# Zhonji_ai8051__Board1_Schematic1__2_P2.net
KiCad netlist of a schematic drawn in Altium Designer
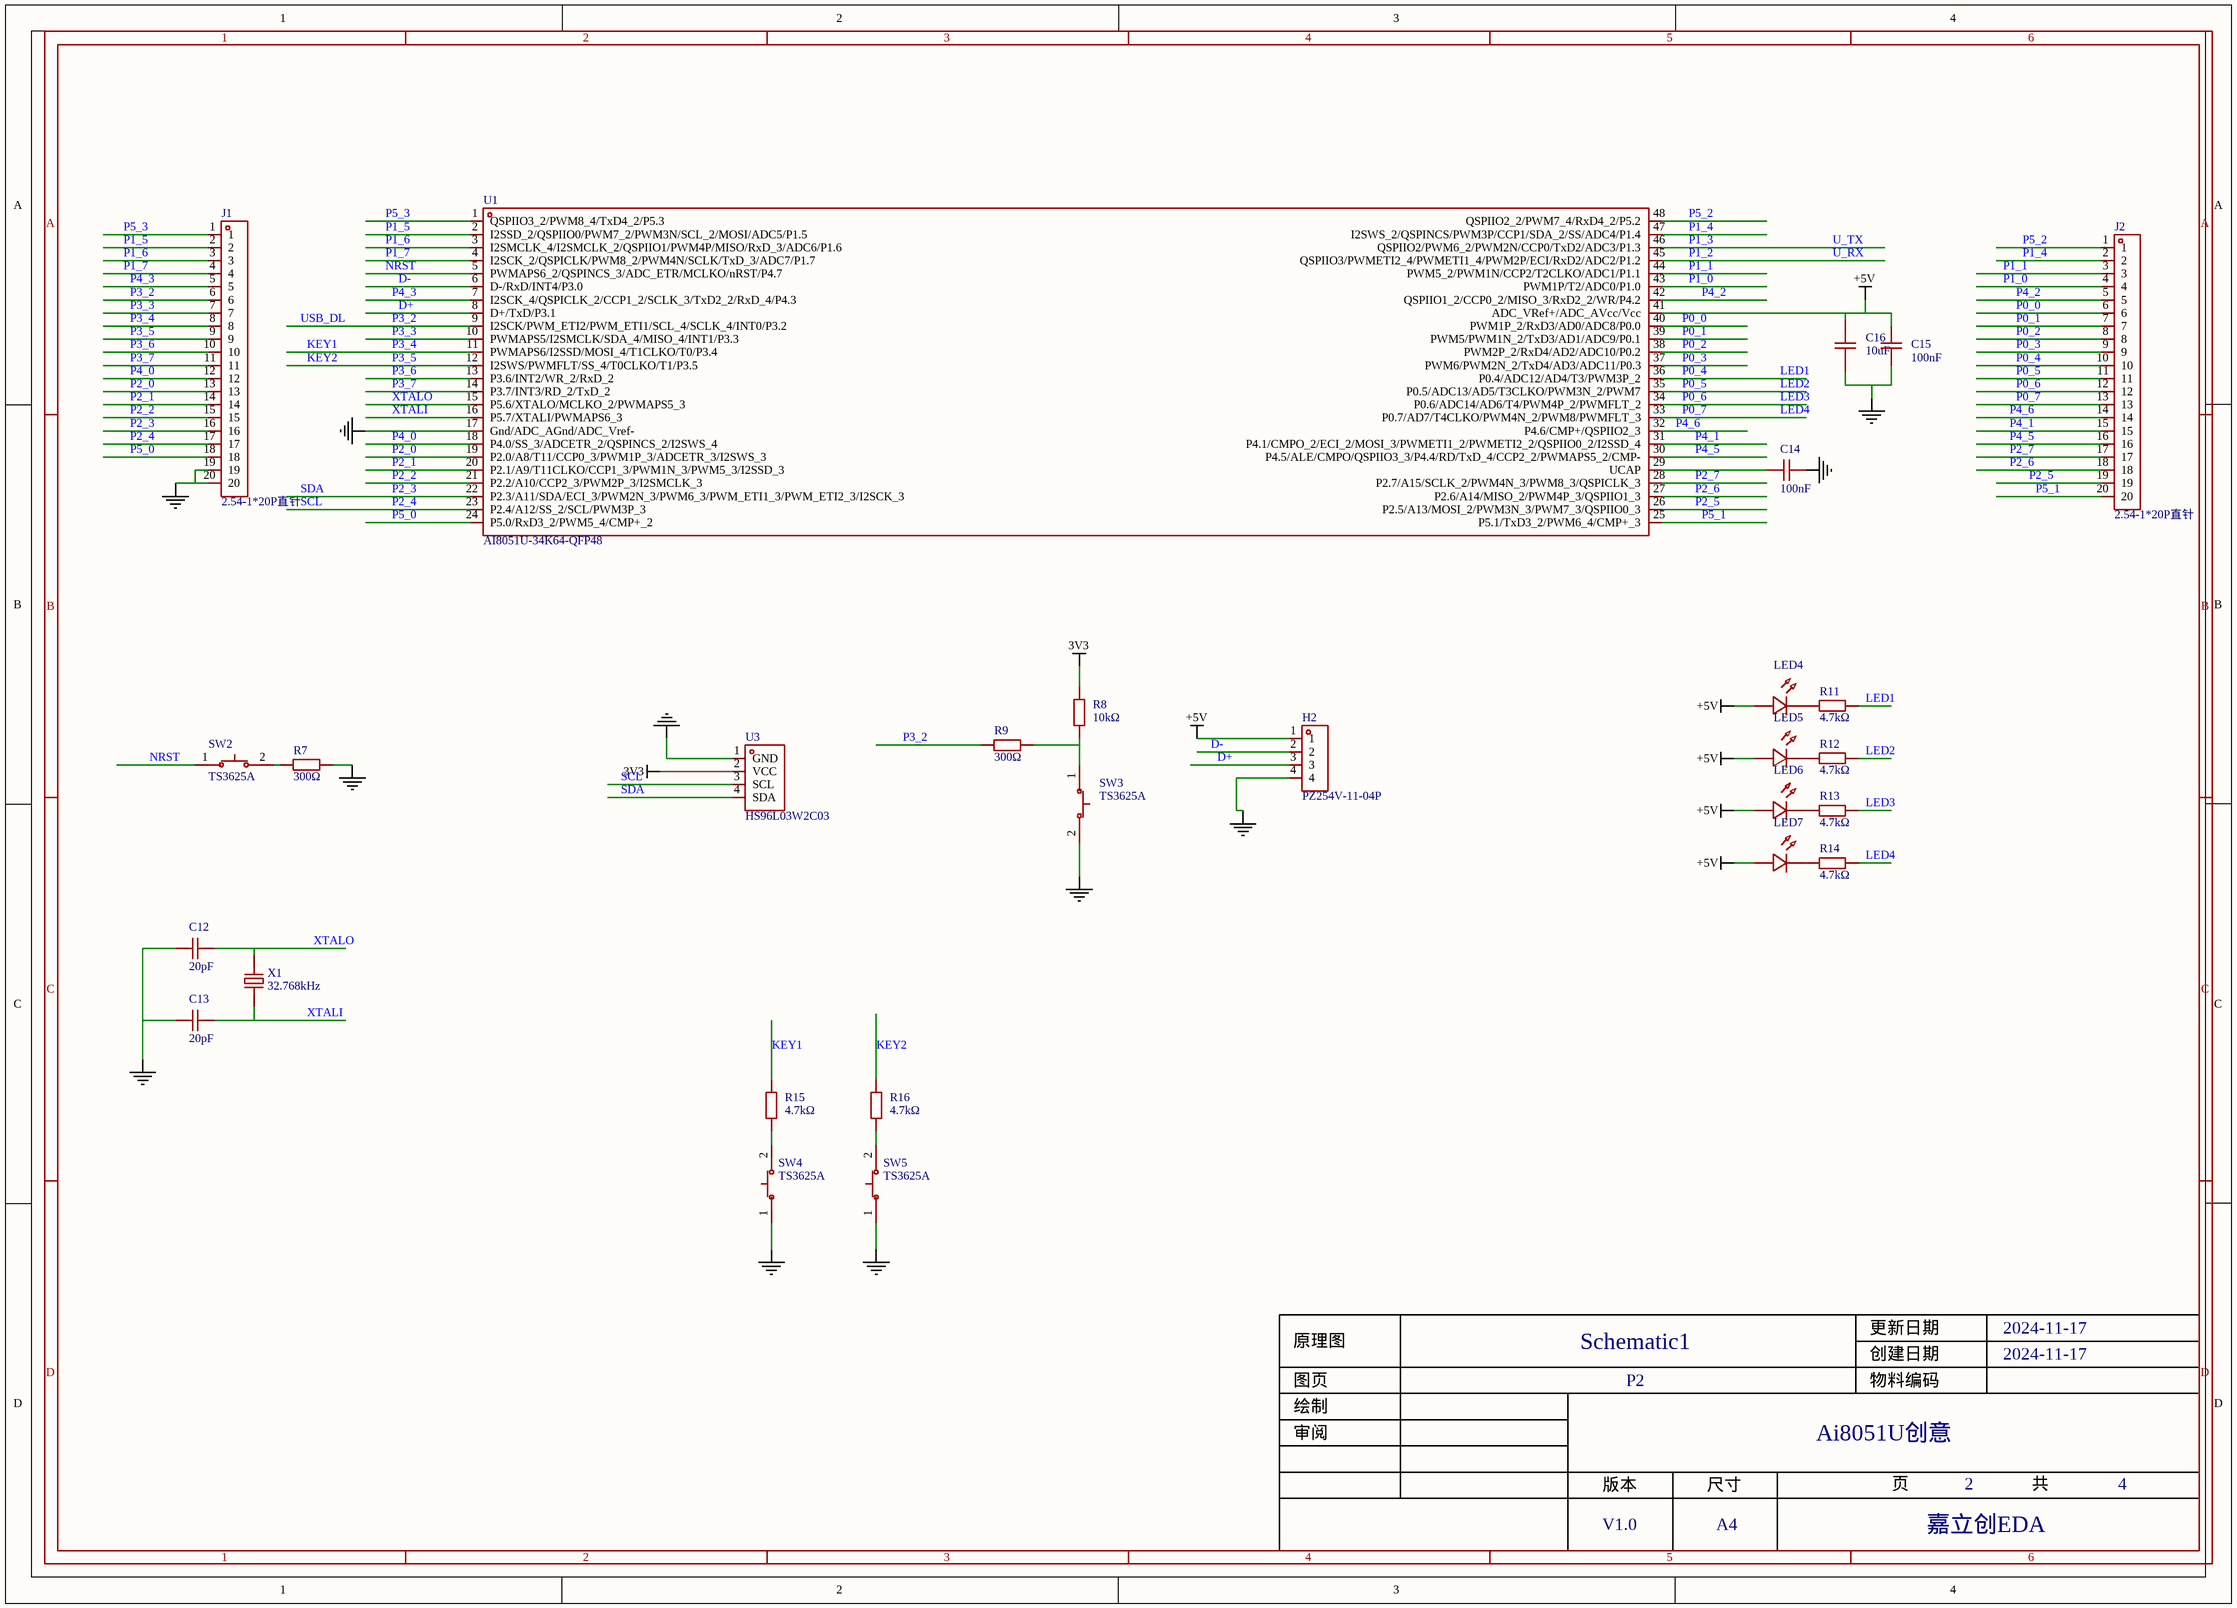
[diagram p0: Zhonji_ai8051__Board1_Schematic1__2_P2.schdoc]

(export (version "E")
  (design (tool "Eeschema 10.0.6"))
  (components
    (comp (ref "C12")
      (value "20pF")
      (footprint "C0603")
      (description "容值:20pF;精度:±5%;额定电压:50V;材质(温度系数):C0G;")
      (fields
        (field (name "MANUFACTURER") "SAMSUNG(三星)")
        (field (name "MANUFACTURER PART") "CL10C200JB8NNNC")
      )
      (libsource (lib "altium-import") (part "root_0_CL10C200JB8NNNC_"))
    )
    (comp (ref "C13")
      (value "20pF")
      (footprint "C0603")
      (description "容值:20pF;精度:±5%;额定电压:50V;材质(温度系数):C0G;")
      (fields
        (field (name "MANUFACTURER") "SAMSUNG(三星)")
        (field (name "MANUFACTURER PART") "CL10C200JB8NNNC")
      )
      (libsource (lib "altium-import") (part "root_0_CL10C200JB8NNNC_"))
    )
    (comp (ref "C14")
      (value "100nF")
      (footprint "C0603")
      (description "容值:100nF;精度:±10%;额定电压:50V;材质(温度系数):2X1;")
      (fields
        (field (name "MANUFACTURER") "TORCH(火炬)")
        (field (name "MANUFACTURER PART") "CT41G-0603-2X1-50V-0.1μF-K(N)")
      )
      (libsource (lib "altium-import") (part "root_2_CT41G-0603-2X1-50V-0.1μF-K(N)_"))
    )
    (comp (ref "C15")
      (value "100nF")
      (footprint "C0603")
      (description "容值:100nF;精度:±10%;额定电压:50V;材质(温度系数):2X1;")
      (fields
        (field (name "MANUFACTURER") "TORCH(火炬)")
        (field (name "MANUFACTURER PART") "CT41G-0603-2X1-50V-0.1μF-K(N)")
      )
      (libsource (lib "altium-import") (part "root_1_CT41G-0603-2X1-50V-0.1μF-K(N)_"))
    )
    (comp (ref "C16")
      (value "10uF")
      (footprint "C0603")
      (description "容值:10uF;精度:±20%;额定电压:25V;材质(温度系数):X5R;")
      (fields
        (field (name "MANUFACTURER") "SAMSUNG(三星)")
        (field (name "MANUFACTURER PART") "CL10A106MA8NRNC")
      )
      (libsource (lib "altium-import") (part "root_1_CL10A106MA8NRNC_"))
    )
    (comp (ref "H2")
      (value "PZ254V-11-04P")
      (footprint "HDR-TH_4P-P2.54-V-M")
      (fields (field (name "MANUFACTURER") "XFCN(兴飞)"))
      (libsource (lib "altium-import") (part "root_0_PZ254V-11-04P_"))
    )
    (comp (ref "J1")
      (value "2.54-1*20P直针")
      (footprint "HDR-TH_20P-P2.54-V-M-1")
      (fields (field (name "MANUFACTURER") "BOOMELE(博穆精密)"))
      (libsource (lib "altium-import") (part "root_0_2.54-1*20P直针_"))
    )
    (comp (ref "J2")
      (value "2.54-1*20P直针")
      (footprint "HDR-TH_20P-P2.54-V-M-1")
      (fields (field (name "MANUFACTURER") "BOOMELE(博穆精密)"))
      (libsource (lib "altium-import") (part "root_0_2.54-1*20P直针_"))
    )
    (comp (ref "LED4")
      (value "LED_0603-B")
      (footprint "LED_0603")
      (libsource (lib "altium-import") (part "root_0_LED_0603-B_"))
    )
    (comp (ref "LED5")
      (value "LED_0603-B")
      (footprint "LED_0603")
      (libsource (lib "altium-import") (part "root_0_LED_0603-B_"))
    )
    (comp (ref "LED6")
      (value "LED_0603-B")
      (footprint "LED_0603")
      (libsource (lib "altium-import") (part "root_0_LED_0603-B_"))
    )
    (comp (ref "LED7")
      (value "LED_0603-B")
      (footprint "LED_0603")
      (libsource (lib "altium-import") (part "root_0_LED_0603-B_"))
    )
    (comp (ref "R7")
      (value "300Ω")
      (footprint "R0603")
      (description "电阻类型:厚膜电阻;阻值:300Ω;精度:±1%;功率:100mW;最大工作电压:75V;温度系数:±100ppm/℃;")
      (fields
        (field (name "MANUFACTURER") "UNI-ROYAL(厚声)")
        (field (name "MANUFACTURER PART") "0603WAF3000T5E")
      )
      (libsource (lib "altium-import") (part "root_0_0603WAF3000T5E_"))
    )
    (comp (ref "R8")
      (value "10kΩ")
      (footprint "R0603")
      (description "电阻类型:厚膜电阻;阻值:10kΩ;精度:±1%;功率:100mW;最大工作电压:75V;温度系数:±100ppm/℃;")
      (fields
        (field (name "MANUFACTURER") "UNI-ROYAL(厚声)")
        (field (name "MANUFACTURER PART") "0603WAF1002T5E")
      )
      (libsource (lib "altium-import") (part "root_1_0603WAF1002T5E_"))
    )
    (comp (ref "R9")
      (value "300Ω")
      (footprint "R0603")
      (description "电阻类型:厚膜电阻;阻值:300Ω;精度:±1%;功率:100mW;最大工作电压:75V;温度系数:±100ppm/℃;")
      (fields
        (field (name "MANUFACTURER") "UNI-ROYAL(厚声)")
        (field (name "MANUFACTURER PART") "0603WAF3000T5E")
      )
      (libsource (lib "altium-import") (part "root_0_0603WAF3000T5E_"))
    )
    (comp (ref "R11")
      (value "4.7kΩ")
      (footprint "R0603")
      (description "电阻类型:厚膜电阻;阻值:4.7kΩ;精度:±1%;功率:100mW;最大工作电压:75V;温度系数:±100ppm/℃;")
      (fields
        (field (name "MANUFACTURER") "UNI-ROYAL(厚声)")
        (field (name "MANUFACTURER PART") "0603WAF4701T5E")
      )
      (libsource (lib "altium-import") (part "root_0_0603WAF4701T5E_"))
    )
    (comp (ref "R12")
      (value "4.7kΩ")
      (footprint "R0603")
      (description "电阻类型:厚膜电阻;阻值:4.7kΩ;精度:±1%;功率:100mW;最大工作电压:75V;温度系数:±100ppm/℃;")
      (fields
        (field (name "MANUFACTURER") "UNI-ROYAL(厚声)")
        (field (name "MANUFACTURER PART") "0603WAF4701T5E")
      )
      (libsource (lib "altium-import") (part "root_0_0603WAF4701T5E_"))
    )
    (comp (ref "R13")
      (value "4.7kΩ")
      (footprint "R0603")
      (description "电阻类型:厚膜电阻;阻值:4.7kΩ;精度:±1%;功率:100mW;最大工作电压:75V;温度系数:±100ppm/℃;")
      (fields
        (field (name "MANUFACTURER") "UNI-ROYAL(厚声)")
        (field (name "MANUFACTURER PART") "0603WAF4701T5E")
      )
      (libsource (lib "altium-import") (part "root_0_0603WAF4701T5E_"))
    )
    (comp (ref "R14")
      (value "4.7kΩ")
      (footprint "R0603")
      (description "电阻类型:厚膜电阻;阻值:4.7kΩ;精度:±1%;功率:100mW;最大工作电压:75V;温度系数:±100ppm/℃;")
      (fields
        (field (name "MANUFACTURER") "UNI-ROYAL(厚声)")
        (field (name "MANUFACTURER PART") "0603WAF4701T5E")
      )
      (libsource (lib "altium-import") (part "root_0_0603WAF4701T5E_"))
    )
    (comp (ref "R15")
      (value "4.7kΩ")
      (footprint "R0603")
      (description "电阻类型:厚膜电阻;阻值:4.7kΩ;精度:±1%;功率:100mW;最大工作电压:75V;温度系数:±100ppm/℃;")
      (fields
        (field (name "MANUFACTURER") "UNI-ROYAL(厚声)")
        (field (name "MANUFACTURER PART") "0603WAF4701T5E")
      )
      (libsource (lib "altium-import") (part "root_1_0603WAF4701T5E_"))
    )
    (comp (ref "R16")
      (value "4.7kΩ")
      (footprint "R0603")
      (description "电阻类型:厚膜电阻;阻值:4.7kΩ;精度:±1%;功率:100mW;最大工作电压:75V;温度系数:±100ppm/℃;")
      (fields
        (field (name "MANUFACTURER") "UNI-ROYAL(厚声)")
        (field (name "MANUFACTURER PART") "0603WAF4701T5E")
      )
      (libsource (lib "altium-import") (part "root_1_0603WAF4701T5E_"))
    )
    (comp (ref "SW2")
      (value "TS3625A")
      (footprint "KEY-SMD_L6.0-W3.5-LS8.4")
      (fields (field (name "MANUFACTURER") "SHOU HAN(首韩)"))
      (libsource (lib "altium-import") (part "root_0_TS3625A_"))
    )
    (comp (ref "SW3")
      (value "TS3625A")
      (footprint "KEY-SMD_L6.0-W3.5-LS8.4")
      (fields (field (name "MANUFACTURER") "SHOU HAN(首韩)"))
      (libsource (lib "altium-import") (part "root_3_TS3625A_"))
    )
    (comp (ref "SW4")
      (value "TS3625A")
      (footprint "KEY-SMD_L6.0-W3.5-LS8.4")
      (fields (field (name "MANUFACTURER") "SHOU HAN(首韩)"))
      (libsource (lib "altium-import") (part "root_1_TS3625A_"))
    )
    (comp (ref "SW5")
      (value "TS3625A")
      (footprint "KEY-SMD_L6.0-W3.5-LS8.4")
      (fields (field (name "MANUFACTURER") "SHOU HAN(首韩)"))
      (libsource (lib "altium-import") (part "root_1_TS3625A_"))
    )
    (comp (ref "U1")
      (value "AI8051U-34K64-QFP48")
      (footprint "LQFP-48_L7.0-W7.0-P0.50-LS9.0-BL_1")
      (description "硬件浮点/硬件三角函数 跑100MHz, 32位8051-CPU 跑 42MHz，PWM 有硬件移相功能，DMA支持外设到外设，DMA支持PWM")
      (fields (field (name "MANUFACTURER") "STC"))
      (libsource (lib "altium-import") (part "root_0_AI8051U-34K64-QFP48_"))
    )
    (comp (ref "U3")
      (value "HS96L03W2C03")
      (footprint "OLED-TH_L27.8-W27.2-P2.54_C9900033791")
      (description "主控芯片:SSD1315;接口类型:I2C;尺寸(inch):0.96;像素分辨率:128x64;")
      (fields (field (name "MANUFACTURER") "HS(汉昇)"))
      (libsource (lib "altium-import") (part "root_0_HS96L03W2C03_"))
    )
    (comp (ref "X1")
      (value "32.768kHz")
      (footprint "OSC-SMD_L3.2-W1.5")
      (description "晶振类型:贴片晶振;频率:32.768kHz;常温频差:±20ppm;外接负载电容:12.5pF;频率稳定度(全温):-;")
      (fields (field (name "MANUFACTURER") "YXC(扬兴晶振)") (field (name "MANUFACTURER PART") "X321532768KGD2SI"))
      (libsource (lib "altium-import") (part "root_1_X321532768KGD2SI_"))
    )
  )
  (nets
    (net (code "1") (name "+5V") (class "Default")
      (node (ref "C15") (pin "2") (pinfunction "2_2") (pintype "passive"))
      (node (ref "C16") (pin "2") (pinfunction "2_2") (pintype "passive"))
      (node (ref "H2") (pin "1") (pinfunction "1_1") (pintype "passive"))
      (node (ref "LED4") (pin "2") (pinfunction "A_2") (pintype "passive"))
      (node (ref "LED5") (pin "2") (pinfunction "A_2") (pintype "passive"))
      (node (ref "LED6") (pin "2") (pinfunction "A_2") (pintype "passive"))
      (node (ref "LED7") (pin "2") (pinfunction "A_2") (pintype "passive"))
      (node (ref "U1") (pin "41") (pinfunction "ADC_VRef+/ADC_AVcc/Vcc_41") (pintype "passive"))
    )
    (net (code "2") (name "/D+") (class "Default")
      (node (ref "H2") (pin "3") (pinfunction "3_3") (pintype "passive"))
      (node (ref "U1") (pin "8") (pinfunction "D+/TxD/P3.1_8") (pintype "passive"))
    )
    (net (code "3") (name "/D-") (class "Default")
      (node (ref "H2") (pin "2") (pinfunction "2_2") (pintype "passive"))
      (node (ref "U1") (pin "6") (pinfunction "D-/RxD/INT4/P3.0_6") (pintype "passive"))
    )
    (net (code "4") (name "/KEY1") (class "Default")
      (node (ref "J1") (pin "8") (pinfunction "8_8") (pintype "passive"))
      (node (ref "R15") (pin "2") (pinfunction "2_2") (pintype "passive"))
      (node (ref "U1") (pin "11") (pinfunction "PWMAPS6/I2SSD/MOSI_4/T1CLKO/T0/P3.4_11") (pintype "passive"))
    )
    (net (code "5") (name "/KEY2") (class "Default")
      (node (ref "J1") (pin "9") (pinfunction "9_9") (pintype "passive"))
      (node (ref "R16") (pin "2") (pinfunction "2_2") (pintype "passive"))
      (node (ref "U1") (pin "12") (pinfunction "I2SWS/PWMFLT/SS_4/T0CLKO/T1/P3.5_12") (pintype "passive"))
    )
    (net (code "6") (name "/LED1") (class "Default")
      (node (ref "J2") (pin "10") (pinfunction "10_10") (pintype "passive"))
      (node (ref "R11") (pin "2") (pinfunction "2_2") (pintype "passive"))
      (node (ref "U1") (pin "36") (pinfunction "P0.4/ADC12/AD4/T3/PWM3P_2_36") (pintype "passive"))
    )
    (net (code "7") (name "/LED2") (class "Default")
      (node (ref "J2") (pin "11") (pinfunction "11_11") (pintype "passive"))
      (node (ref "R12") (pin "2") (pinfunction "2_2") (pintype "passive"))
      (node (ref "U1") (pin "35") (pinfunction "P0.5/ADC13/AD5/T3CLKO/PWM3N_2/PWM7_35") (pintype "passive"))
    )
    (net (code "8") (name "/LED3") (class "Default")
      (node (ref "J2") (pin "12") (pinfunction "12_12") (pintype "passive"))
      (node (ref "R13") (pin "2") (pinfunction "2_2") (pintype "passive"))
      (node (ref "U1") (pin "34") (pinfunction "P0.6/ADC14/AD6/T4/PWM4P_2/PWMFLT_2_34") (pintype "passive"))
    )
    (net (code "9") (name "/LED4") (class "Default")
      (node (ref "J2") (pin "13") (pinfunction "13_13") (pintype "passive"))
      (node (ref "R14") (pin "2") (pinfunction "2_2") (pintype "passive"))
      (node (ref "U1") (pin "33") (pinfunction "P0.7/AD7/T4CLKO/PWM4N_2/PWM8/PWMFLT_3_33") (pintype "passive"))
    )
    (net (code "10") (name "/NRST") (class "Default")
      (node (ref "SW2") (pin "1") (pinfunction "1_1") (pintype "passive"))
      (node (ref "U1") (pin "5") (pinfunction "PWMAPS6_2/QSPINCS_3/ADC_ETR/MCLKO/nRST/P4.7_5") (pintype "passive"))
    )
    (net (code "11") (name "/P0_0") (class "Default")
      (node (ref "J2") (pin "6") (pinfunction "6_6") (pintype "passive"))
      (node (ref "U1") (pin "40") (pinfunction "PWM1P_2/RxD3/AD0/ADC8/P0.0_40") (pintype "passive"))
    )
    (net (code "12") (name "/P0_1") (class "Default")
      (node (ref "J2") (pin "7") (pinfunction "7_7") (pintype "passive"))
      (node (ref "U1") (pin "39") (pinfunction "PWM5/PWM1N_2/TxD3/AD1/ADC9/P0.1_39") (pintype "passive"))
    )
    (net (code "13") (name "/P0_2") (class "Default")
      (node (ref "J2") (pin "8") (pinfunction "8_8") (pintype "passive"))
      (node (ref "U1") (pin "38") (pinfunction "PWM2P_2/RxD4/AD2/ADC10/P0.2_38") (pintype "passive"))
    )
    (net (code "14") (name "/P0_3") (class "Default")
      (node (ref "J2") (pin "9") (pinfunction "9_9") (pintype "passive"))
      (node (ref "U1") (pin "37") (pinfunction "PWM6/PWM2N_2/TxD4/AD3/ADC11/P0.3_37") (pintype "passive"))
    )
    (net (code "15") (name "/P1_0") (class "Default")
      (node (ref "J2") (pin "4") (pinfunction "4_4") (pintype "passive"))
      (node (ref "U1") (pin "43") (pinfunction "PWM1P/T2/ADC0/P1.0_43") (pintype "passive"))
    )
    (net (code "16") (name "/P1_1") (class "Default")
      (node (ref "J2") (pin "3") (pinfunction "3_3") (pintype "passive"))
      (node (ref "U1") (pin "44") (pinfunction "PWM5_2/PWM1N/CCP2/T2CLKO/ADC1/P1.1_44") (pintype "passive"))
    )
    (net (code "17") (name "/P1_2") (class "Default")
      (node (ref "U1") (pin "45") (pinfunction "QSPIIO3/PWMETI2_4/PWMETI1_4/PWM2P/ECI/RxD2/ADC2/P1.2_45") (pintype "passive"))
    )
    (net (code "18") (name "/P1_3") (class "Default")
      (node (ref "U1") (pin "46") (pinfunction "QSPIIO2/PWM6_2/PWM2N/CCP0/TxD2/ADC3/P1.3_46") (pintype "passive"))
    )
    (net (code "19") (name "/P1_4") (class "Default")
      (node (ref "J2") (pin "2") (pinfunction "2_2") (pintype "passive"))
      (node (ref "U1") (pin "47") (pinfunction "I2SWS_2/QSPINCS/PWM3P/CCP1/SDA_2/SS/ADC4/P1.4_47") (pintype "passive"))
    )
    (net (code "20") (name "/P1_5") (class "Default")
      (node (ref "J1") (pin "2") (pinfunction "2_2") (pintype "passive"))
      (node (ref "U1") (pin "2") (pinfunction "I2SSD_2/QSPIIO0/PWM7_2/PWM3N/SCL_2/MOSI/ADC5/P1.5_2") (pintype "passive"))
    )
    (net (code "21") (name "/P1_6") (class "Default")
      (node (ref "J1") (pin "3") (pinfunction "3_3") (pintype "passive"))
      (node (ref "U1") (pin "3") (pinfunction "I2SMCLK_4/I2SMCLK_2/QSPIIO1/PWM4P/MISO/RxD_3/ADC6/P1.6_3") (pintype "passive"))
    )
    (net (code "22") (name "/P1_7") (class "Default")
      (node (ref "J1") (pin "4") (pinfunction "4_4") (pintype "passive"))
      (node (ref "U1") (pin "4") (pinfunction "I2SCK_2/QSPICLK/PWM8_2/PWM4N/SCLK/TxD_3/ADC7/P1.7_4") (pintype "passive"))
    )
    (net (code "23") (name "/P2_0") (class "Default")
      (node (ref "J1") (pin "13") (pinfunction "13_13") (pintype "passive"))
      (node (ref "U1") (pin "19") (pinfunction "P2.0/A8/T11/CCP0_3/PWM1P_3/ADCETR_3/I2SWS_3_19") (pintype "passive"))
    )
    (net (code "24") (name "/P2_1") (class "Default")
      (node (ref "J1") (pin "14") (pinfunction "14_14") (pintype "passive"))
      (node (ref "U1") (pin "20") (pinfunction "P2.1/A9/T11CLKO/CCP1_3/PWM1N_3/PWM5_3/I2SSD_3_20") (pintype "passive"))
    )
    (net (code "25") (name "/P2_2") (class "Default")
      (node (ref "J1") (pin "15") (pinfunction "15_15") (pintype "passive"))
      (node (ref "U1") (pin "21") (pinfunction "P2.2/A10/CCP2_3/PWM2P_3/I2SMCLK_3_21") (pintype "passive"))
    )
    (net (code "26") (name "/P2_3") (class "Default")
      (node (ref "J1") (pin "16") (pinfunction "16_16") (pintype "passive"))
      (node (ref "U1") (pin "22") (pinfunction "P2.3/A11/SDA/ECI_3/PWM2N_3/PWM6_3/PWM_ETI1_3/PWM_ETI2_3/I2SCK_3_22") (pintype "passive"))
      (node (ref "U3") (pin "4") (pinfunction "SDA_4") (pintype "passive"))
    )
    (net (code "27") (name "/P2_4") (class "Default")
      (node (ref "J1") (pin "17") (pinfunction "17_17") (pintype "passive"))
      (node (ref "U1") (pin "23") (pinfunction "P2.4/A12/SS_2/SCL/PWM3P_3_23") (pintype "passive"))
      (node (ref "U3") (pin "3") (pinfunction "SCL_3") (pintype "passive"))
    )
    (net (code "28") (name "/P2_5") (class "Default")
      (node (ref "J2") (pin "19") (pinfunction "19_19") (pintype "passive"))
      (node (ref "U1") (pin "26") (pinfunction "P2.5/A13/MOSI_2/PWM3N_3/PWM7_3/QSPIIO0_3_26") (pintype "passive"))
    )
    (net (code "29") (name "/P2_6") (class "Default")
      (node (ref "J2") (pin "18") (pinfunction "18_18") (pintype "passive"))
      (node (ref "U1") (pin "27") (pinfunction "P2.6/A14/MISO_2/PWM4P_3/QSPIIO1_3_27") (pintype "passive"))
    )
    (net (code "30") (name "/P2_7") (class "Default")
      (node (ref "J2") (pin "17") (pinfunction "17_17") (pintype "passive"))
      (node (ref "U1") (pin "28") (pinfunction "P2.7/A15/SCLK_2/PWM4N_3/PWM8_3/QSPICLK_3_28") (pintype "passive"))
    )
    (net (code "31") (name "/P3_2") (class "Default")
      (node (ref "J1") (pin "6") (pinfunction "6_6") (pintype "passive"))
      (node (ref "R9") (pin "1") (pinfunction "1_1") (pintype "passive"))
      (node (ref "U1") (pin "9") (pinfunction "I2SCK/PWM_ETI2/PWM_ETI1/SCL_4/SCLK_4/INT0/P3.2_9") (pintype "passive"))
    )
    (net (code "32") (name "/P3_3") (class "Default")
      (node (ref "J1") (pin "7") (pinfunction "7_7") (pintype "passive"))
      (node (ref "U1") (pin "10") (pinfunction "PWMAPS5/I2SMCLK/SDA_4/MISO_4/INT1/P3.3_10") (pintype "passive"))
    )
    (net (code "33") (name "/P3_6") (class "Default")
      (node (ref "J1") (pin "10") (pinfunction "10_10") (pintype "passive"))
      (node (ref "U1") (pin "13") (pinfunction "P3.6/INT2/WR_2/RxD_2_13") (pintype "passive"))
    )
    (net (code "34") (name "/P3_7") (class "Default")
      (node (ref "J1") (pin "11") (pinfunction "11_11") (pintype "passive"))
      (node (ref "U1") (pin "14") (pinfunction "P3.7/INT3/RD_2/TxD_2_14") (pintype "passive"))
    )
    (net (code "35") (name "/P4_0") (class "Default")
      (node (ref "J1") (pin "12") (pinfunction "12_12") (pintype "passive"))
      (node (ref "U1") (pin "18") (pinfunction "P4.0/SS_3/ADCETR_2/QSPINCS_2/I2SWS_4_18") (pintype "passive"))
    )
    (net (code "36") (name "/P4_1") (class "Default")
      (node (ref "J2") (pin "15") (pinfunction "15_15") (pintype "passive"))
      (node (ref "U1") (pin "31") (pinfunction "P4.1/CMPO_2/ECI_2/MOSI_3/PWMETI1_2/PWMETI2_2/QSPIIO0_2/I2SSD_4_31") (pintype "passive"))
    )
    (net (code "37") (name "/P4_2") (class "Default")
      (node (ref "J2") (pin "5") (pinfunction "5_5") (pintype "passive"))
      (node (ref "U1") (pin "42") (pinfunction "QSPIIO1_2/CCP0_2/MISO_3/RxD2_2/WR/P4.2_42") (pintype "passive"))
    )
    (net (code "38") (name "/P4_3") (class "Default")
      (node (ref "J1") (pin "5") (pinfunction "5_5") (pintype "passive"))
      (node (ref "U1") (pin "7") (pinfunction "I2SCK_4/QSPICLK_2/CCP1_2/SCLK_3/TxD2_2/RxD_4/P4.3_7") (pintype "passive"))
    )
    (net (code "39") (name "/P4_5") (class "Default")
      (node (ref "J2") (pin "16") (pinfunction "16_16") (pintype "passive"))
      (node (ref "U1") (pin "30") (pinfunction "P4.5/ALE/CMPO/QSPIIO3_3/P4.4/RD/TxD_4/CCP2_2/PWMAPS5_2/CMP-_30") (pintype "passive"))
    )
    (net (code "40") (name "/P4_6") (class "Default")
      (node (ref "J2") (pin "14") (pinfunction "14_14") (pintype "passive"))
      (node (ref "U1") (pin "32") (pinfunction "P4.6/CMP+/QSPIIO2_3_32") (pintype "passive"))
    )
    (net (code "41") (name "/P5_0") (class "Default")
      (node (ref "J1") (pin "18") (pinfunction "18_18") (pintype "passive"))
      (node (ref "U1") (pin "24") (pinfunction "P5.0/RxD3_2/PWM5_4/CMP+_2_24") (pintype "passive"))
    )
    (net (code "42") (name "/P5_1") (class "Default")
      (node (ref "J2") (pin "20") (pinfunction "20_20") (pintype "passive"))
      (node (ref "U1") (pin "25") (pinfunction "P5.1/TxD3_2/PWM6_4/CMP+_3_25") (pintype "passive"))
    )
    (net (code "43") (name "/P5_2") (class "Default")
      (node (ref "J2") (pin "1") (pinfunction "1_1") (pintype "passive"))
      (node (ref "U1") (pin "48") (pinfunction "QSPIIO2_2/PWM7_4/RxD4_2/P5.2_48") (pintype "passive"))
    )
    (net (code "44") (name "/P5_3") (class "Default")
      (node (ref "J1") (pin "1") (pinfunction "1_1") (pintype "passive"))
      (node (ref "U1") (pin "1") (pinfunction "QSPIIO3_2/PWM8_4/TxD4_2/P5.3_1") (pintype "passive"))
    )
    (net (code "45") (name "/XTALI") (class "Default")
      (node (ref "C13") (pin "2") (pinfunction "2_2") (pintype "passive"))
      (node (ref "U1") (pin "16") (pinfunction "P5.7/XTALI/PWMAPS6_3_16") (pintype "passive"))
      (node (ref "X1") (pin "1") (pinfunction "1_1") (pintype "passive"))
    )
    (net (code "46") (name "/XTALO") (class "Default")
      (node (ref "C12") (pin "2") (pinfunction "2_2") (pintype "passive"))
      (node (ref "U1") (pin "15") (pinfunction "P5.6/XTALO/MCLKO_2/PWMAPS5_3_15") (pintype "passive"))
      (node (ref "X1") (pin "2") (pinfunction "2_2") (pintype "passive"))
    )
    (net (code "47") (name "3V3") (class "Default")
      (node (ref "R8") (pin "2") (pinfunction "2_2") (pintype "passive"))
      (node (ref "U3") (pin "2") (pinfunction "VCC_2") (pintype "passive"))
    )
    (net (code "48") (name "GND") (class "Default")
      (node (ref "C12") (pin "1") (pinfunction "1_1") (pintype "passive"))
      (node (ref "C13") (pin "1") (pinfunction "1_1") (pintype "passive"))
      (node (ref "C14") (pin "1") (pinfunction "1_1") (pintype "passive"))
      (node (ref "C15") (pin "1") (pinfunction "1_1") (pintype "passive"))
      (node (ref "C16") (pin "1") (pinfunction "1_1") (pintype "passive"))
      (node (ref "H2") (pin "4") (pinfunction "4_4") (pintype "passive"))
      (node (ref "J1") (pin "19") (pinfunction "19_19") (pintype "passive"))
      (node (ref "J1") (pin "20") (pinfunction "20_20") (pintype "passive"))
      (node (ref "R7") (pin "2") (pinfunction "2_2") (pintype "passive"))
      (node (ref "SW3") (pin "2") (pinfunction "2_2") (pintype "passive"))
      (node (ref "SW4") (pin "1") (pinfunction "1_1") (pintype "passive"))
      (node (ref "SW5") (pin "1") (pinfunction "1_1") (pintype "passive"))
      (node (ref "U1") (pin "17") (pinfunction "Gnd/ADC_AGnd/ADC_Vref-_17") (pintype "passive"))
      (node (ref "U3") (pin "1") (pinfunction "GND_1") (pintype "passive"))
    )
    (net (code "49") (name "Net-(LED4-C)") (class "Default")
      (node (ref "LED4") (pin "1") (pinfunction "C_1") (pintype "passive"))
      (node (ref "R11") (pin "1") (pinfunction "1_1") (pintype "passive"))
    )
    (net (code "50") (name "Net-(LED5-C)") (class "Default")
      (node (ref "LED5") (pin "1") (pinfunction "C_1") (pintype "passive"))
      (node (ref "R12") (pin "1") (pinfunction "1_1") (pintype "passive"))
    )
    (net (code "51") (name "Net-(LED6-C)") (class "Default")
      (node (ref "LED6") (pin "1") (pinfunction "C_1") (pintype "passive"))
      (node (ref "R13") (pin "1") (pinfunction "1_1") (pintype "passive"))
    )
    (net (code "52") (name "Net-(LED7-C)") (class "Default")
      (node (ref "LED7") (pin "1") (pinfunction "C_1") (pintype "passive"))
      (node (ref "R14") (pin "1") (pinfunction "1_1") (pintype "passive"))
    )
    (net (code "53") (name "Net-(R7-Pad1)") (class "Default")
      (node (ref "R7") (pin "1") (pinfunction "1_1") (pintype "passive"))
      (node (ref "SW2") (pin "2") (pinfunction "2_2") (pintype "passive"))
    )
    (net (code "54") (name "Net-(R8-Pad1)") (class "Default")
      (node (ref "R8") (pin "1") (pinfunction "1_1") (pintype "passive"))
      (node (ref "R9") (pin "2") (pinfunction "2_2") (pintype "passive"))
      (node (ref "SW3") (pin "1") (pinfunction "1_1") (pintype "passive"))
    )
    (net (code "55") (name "Net-(R15-Pad1)") (class "Default")
      (node (ref "R15") (pin "1") (pinfunction "1_1") (pintype "passive"))
      (node (ref "SW4") (pin "2") (pinfunction "2_2") (pintype "passive"))
    )
    (net (code "56") (name "Net-(R16-Pad1)") (class "Default")
      (node (ref "R16") (pin "1") (pinfunction "1_1") (pintype "passive"))
      (node (ref "SW5") (pin "2") (pinfunction "2_2") (pintype "passive"))
    )
    (net (code "57") (name "Net-(U1-UCAP)") (class "Default")
      (node (ref "C14") (pin "2") (pinfunction "2_2") (pintype "passive"))
      (node (ref "U1") (pin "29") (pinfunction "UCAP_29") (pintype "passive"))
    )
  )
)
